# lp_prog.net
KiCad netlist of a schematic drawn in EAGLE
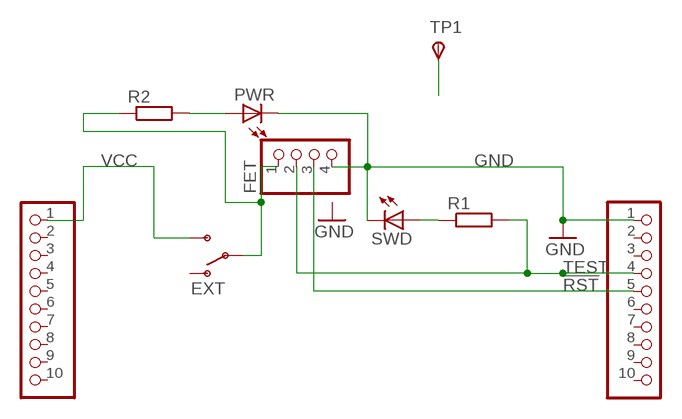
[diagram p0: schematic, sheet 1]

(export (version "E")
  (design (tool "Eeschema 10.0.6"))
  (components
    (comp (ref "FET")
      (value "FET")
      (footprint "eagle-import:1X04")
      (libsource (lib "eagle-import") (part "PINHD-1X4"))
    )
    (comp (ref "J1")
      (value "J1")
      (footprint "eagle-import:1X10")
      (libsource (lib "eagle-import") (part "PINHD-1X10"))
    )
    (comp (ref "J2")
      (value "J2")
      (footprint "eagle-import:1X10")
      (libsource (lib "eagle-import") (part "PINHD-1X10"))
    )
    (comp (ref "ON")
      (value "EXT")
      (footprint "eagle-import:SWITCH-SPDT")
      (libsource (lib "eagle-import") (part "SWITCH-SPSTPTH"))
    )
    (comp (ref "PWR")
      (value "PWR")
      (footprint "eagle-import:CHIPLED_1206")
      (libsource (lib "eagle-import") (part "LEDCHIPLED_1206"))
    )
    (comp (ref "R1")
      (value "470")
      (footprint "eagle-import:R0805")
      (libsource (lib "eagle-import") (part "R-EU_R0805"))
    )
    (comp (ref "R2")
      (value "470")
      (footprint "eagle-import:R0805")
      (libsource (lib "eagle-import") (part "R-EU_R0805"))
    )
    (comp (ref "SWD")
      (value "SWD")
      (footprint "eagle-import:CHIPLED_1206")
      (libsource (lib "eagle-import") (part "LEDCHIPLED_1206"))
    )
    (comp (ref "TP1")
      (value "TPSTP20R")
      (footprint "eagle-import:TP20R")
      (libsource (lib "eagle-import") (part "TPSTP20R"))
    )
  )
  (nets
    (net (code "1") (name "/TEST") (class "Default")
      (node (ref "FET") (pin "2") (pinfunction "2_2") (pintype "passive"))
      (node (ref "J2") (pin "4") (pinfunction "4_4") (pintype "passive"))
      (node (ref "R1") (pin "2") (pinfunction "2_2") (pintype "passive"))
    )
    (net (code "2") (name "/VCC") (class "Default")
      (node (ref "J1") (pin "1") (pinfunction "1_1") (pintype "passive"))
      (node (ref "ON") (pin "3") (pinfunction "S_3") (pintype "passive"))
    )
    (net (code "3") (name "/~{RST}") (class "Default")
      (node (ref "FET") (pin "3") (pinfunction "3_3") (pintype "passive"))
      (node (ref "J2") (pin "5") (pinfunction "5_5") (pintype "passive"))
    )
    (net (code "4") (name "GND") (class "Default")
      (node (ref "FET") (pin "4") (pinfunction "4_4") (pintype "passive"))
      (node (ref "J2") (pin "1") (pinfunction "1_1") (pintype "passive"))
      (node (ref "PWR") (pin "C") (pinfunction "C_C") (pintype "passive"))
      (node (ref "SWD") (pin "C") (pinfunction "C_C") (pintype "passive"))
    )
    (net (code "5") (name "Net-(ON-P)") (class "Default")
      (node (ref "FET") (pin "1") (pinfunction "1_1") (pintype "passive"))
      (node (ref "ON") (pin "2") (pinfunction "P_2") (pintype "passive"))
      (node (ref "R2") (pin "1") (pinfunction "1_1") (pintype "passive"))
    )
    (net (code "6") (name "Net-(PWR-PadA)") (class "Default")
      (node (ref "PWR") (pin "A") (pinfunction "A_A") (pintype "passive"))
      (node (ref "R2") (pin "2") (pinfunction "2_2") (pintype "passive"))
    )
    (net (code "7") (name "Net-(R1-Pad1)") (class "Default")
      (node (ref "R1") (pin "1") (pinfunction "1_1") (pintype "passive"))
      (node (ref "SWD") (pin "A") (pinfunction "A_A") (pintype "passive"))
    )
    (net (code "8") (name "unconnected-(J1-Pad2)") (class "Default")
      (node (ref "J1") (pin "2") (pinfunction "2_2") (pintype "passive"))
    )
    (net (code "9") (name "unconnected-(J1-Pad3)") (class "Default")
      (node (ref "J1") (pin "3") (pinfunction "3_3") (pintype "passive"))
    )
    (net (code "10") (name "unconnected-(J1-Pad4)") (class "Default")
      (node (ref "J1") (pin "4") (pinfunction "4_4") (pintype "passive"))
    )
    (net (code "11") (name "unconnected-(J1-Pad5)") (class "Default")
      (node (ref "J1") (pin "5") (pinfunction "5_5") (pintype "passive"))
    )
    (net (code "12") (name "unconnected-(J1-Pad6)") (class "Default")
      (node (ref "J1") (pin "6") (pinfunction "6_6") (pintype "passive"))
    )
    (net (code "13") (name "unconnected-(J1-Pad7)") (class "Default")
      (node (ref "J1") (pin "7") (pinfunction "7_7") (pintype "passive"))
    )
    (net (code "14") (name "unconnected-(J1-Pad8)") (class "Default")
      (node (ref "J1") (pin "8") (pinfunction "8_8") (pintype "passive"))
    )
    (net (code "15") (name "unconnected-(J1-Pad9)") (class "Default")
      (node (ref "J1") (pin "9") (pinfunction "9_9") (pintype "passive"))
    )
    (net (code "16") (name "unconnected-(J1-Pad10)") (class "Default")
      (node (ref "J1") (pin "10") (pinfunction "10_10") (pintype "passive"))
    )
    (net (code "17") (name "unconnected-(J2-Pad2)") (class "Default")
      (node (ref "J2") (pin "2") (pinfunction "2_2") (pintype "passive"))
    )
    (net (code "18") (name "unconnected-(J2-Pad3)") (class "Default")
      (node (ref "J2") (pin "3") (pinfunction "3_3") (pintype "passive"))
    )
    (net (code "19") (name "unconnected-(J2-Pad6)") (class "Default")
      (node (ref "J2") (pin "6") (pinfunction "6_6") (pintype "passive"))
    )
    (net (code "20") (name "unconnected-(J2-Pad7)") (class "Default")
      (node (ref "J2") (pin "7") (pinfunction "7_7") (pintype "passive"))
    )
    (net (code "21") (name "unconnected-(J2-Pad8)") (class "Default")
      (node (ref "J2") (pin "8") (pinfunction "8_8") (pintype "passive"))
    )
    (net (code "22") (name "unconnected-(J2-Pad9)") (class "Default")
      (node (ref "J2") (pin "9") (pinfunction "9_9") (pintype "passive"))
    )
    (net (code "23") (name "unconnected-(J2-Pad10)") (class "Default")
      (node (ref "J2") (pin "10") (pinfunction "10_10") (pintype "passive"))
    )
    (net (code "24") (name "unconnected-(ON-O-Pad1)") (class "Default")
      (node (ref "ON") (pin "1") (pinfunction "O_1") (pintype "passive"))
    )
    (net (code "25") (name "unconnected-(TP1-PP-PadTP)") (class "Default")
      (node (ref "TP1") (pin "TP") (pinfunction "PP_TP") (pintype "input"))
    )
  )
)
